# Schematic_Lithium-wemos-shield.net
KiCad netlist of a schematic drawn in EasyEDA
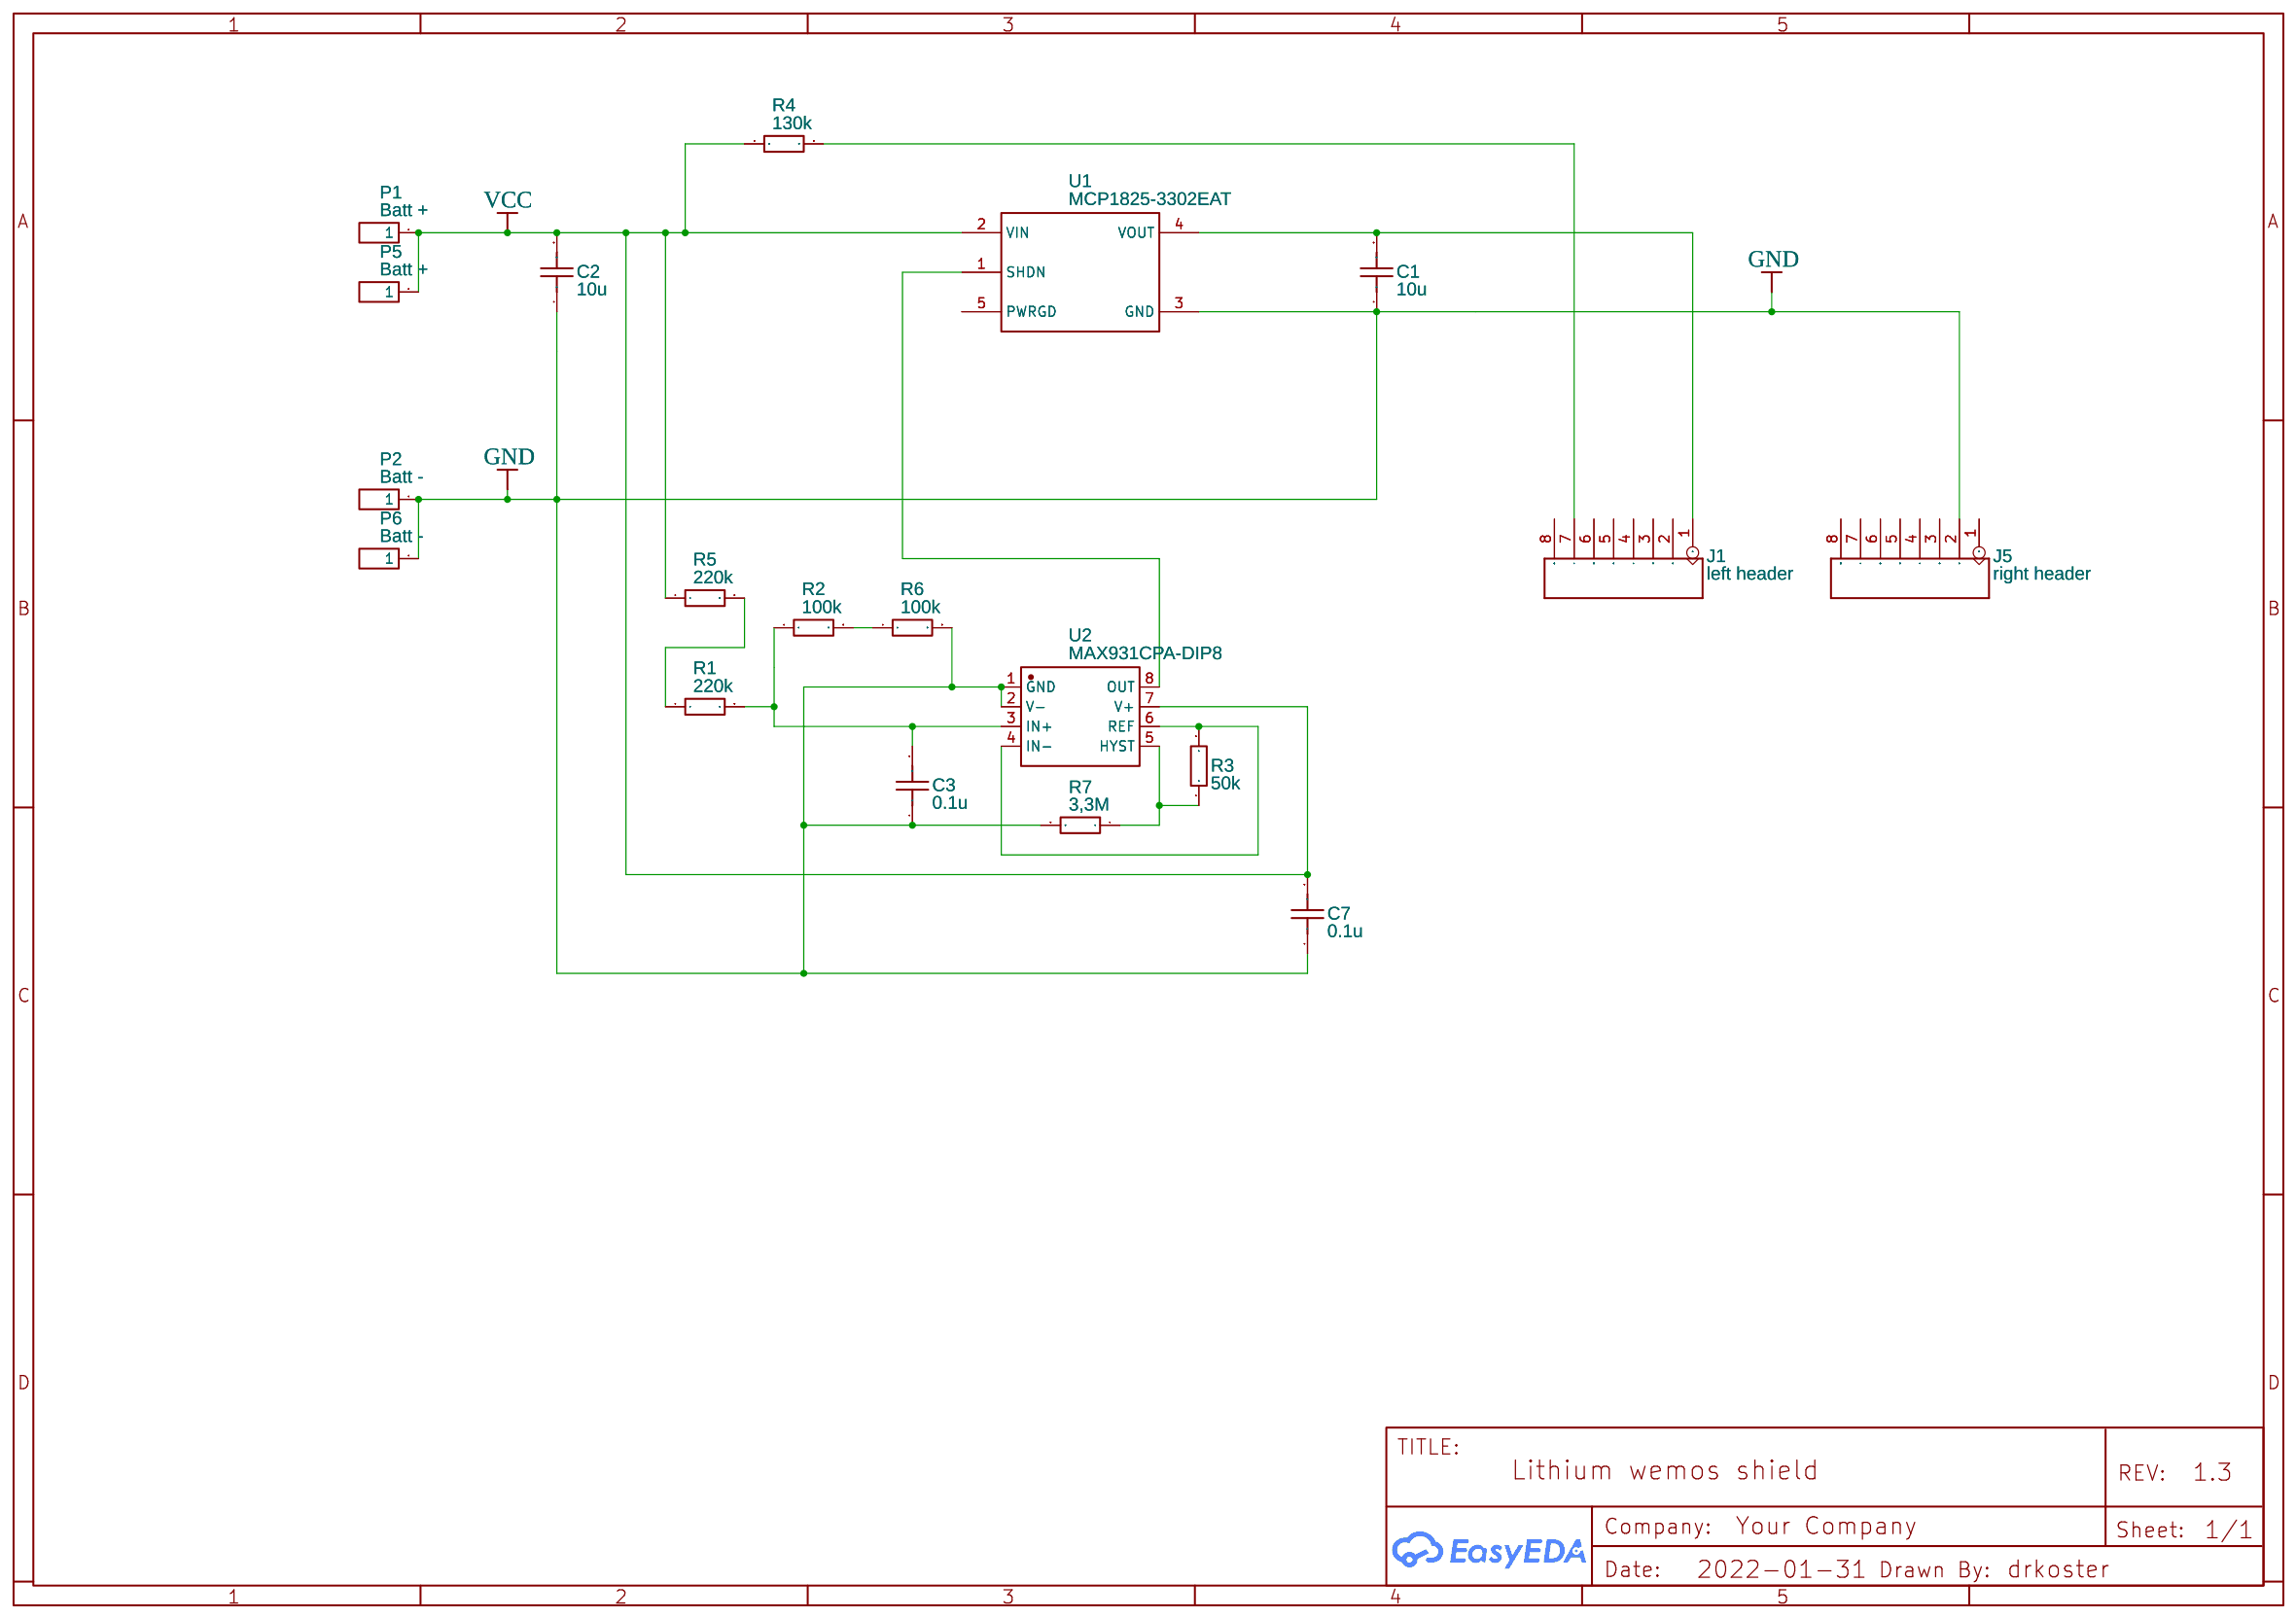
[diagram p0: schematic sheet]

(export (version "E")
  (design (tool "Eeschema 10.0.6"))
  (components
    (comp (ref "C1")
      (value "10u")
      (fields (field (name "BOM_Manufacturer Part") "?"))
      (libsource (lib "") (part "Cap_RAD-0.1_US"))
    )
    (comp (ref "C2")
      (value "10u")
      (fields (field (name "BOM_Manufacturer Part") "?"))
      (libsource (lib "") (part "Cap_RAD-0.1_US"))
    )
    (comp (ref "C3")
      (value "0.1u")
      (fields (field (name "BOM_Manufacturer Part") "?"))
      (libsource (lib "") (part "Cap_RAD-0.1_US"))
    )
    (comp (ref "C7")
      (value "0.1u")
      (fields (field (name "BOM_Manufacturer Part") "?"))
      (libsource (lib "") (part "Cap_RAD-0.1_US"))
    )
    (comp (ref "J1")
      (value "left header")
      (fields (field (name "BOM_Manufacturer Part") "F185-1108A0BSYA5"))
      (libsource (lib "") (part "Unknown_815_-530"))
    )
    (comp (ref "J5")
      (value "right header")
      (fields (field (name "BOM_Manufacturer Part") "F185-1108A0BSYA5"))
      (libsource (lib "") (part "Unknown_960_-530"))
    )
    (comp (ref "P1")
      (value "Batt +")
      (fields
        (field (name "BOM_Manufacturer Part") "Header-Male-2.54_1x1")
        (field (name "BOM_Supplier Part") "C81276")
      )
      (libsource (lib "") (part "Unknown_190_-695"))
    )
    (comp (ref "P2")
      (value "Batt -")
      (fields
        (field (name "BOM_Manufacturer Part") "Header-Male-2.54_1x1")
        (field (name "BOM_Supplier Part") "C81276")
      )
      (libsource (lib "") (part "Unknown_190_-560"))
    )
    (comp (ref "P5")
      (value "Batt +")
      (fields
        (field (name "BOM_Manufacturer Part") "Header-Male-2.54_1x1")
        (field (name "BOM_Supplier Part") "C81276")
      )
      (libsource (lib "") (part "Unknown_190_-665"))
    )
    (comp (ref "P6")
      (value "Batt -")
      (fields
        (field (name "BOM_Manufacturer Part") "Header-Male-2.54_1x1")
        (field (name "BOM_Supplier Part") "C81276")
      )
      (libsource (lib "") (part "Unknown_190_-530"))
    )
    (comp (ref "R1")
      (value "220k")
      (fields
        (field (name "BOM_Manufacturer Part") "MF1W-5.1Ω±1%")
        (field (name "BOM_Supplier Part") "C127239")
      )
      (libsource (lib "") (part "MF1W-5.1Ω±1%"))
    )
    (comp (ref "R2")
      (value "100k")
      (fields
        (field (name "BOM_Manufacturer Part") "MF1W-5.1Ω±1%")
        (field (name "BOM_Supplier Part") "C127239")
      )
      (libsource (lib "") (part "MF1W-5.1Ω±1%"))
    )
    (comp (ref "R3")
      (value "50k")
      (fields
        (field (name "BOM_Manufacturer Part") "MF1W-5.1Ω±1%")
        (field (name "BOM_Supplier Part") "C127239")
      )
      (libsource (lib "") (part "MF1W-5.1Ω±1%_2"))
    )
    (comp (ref "R4")
      (value "130k")
      (fields
        (field (name "BOM_Manufacturer Part") "MF1W-5.1Ω±1%")
        (field (name "BOM_Supplier Part") "C127239")
      )
      (libsource (lib "") (part "MF1W-5.1Ω±1%"))
    )
    (comp (ref "R5")
      (value "220k")
      (fields
        (field (name "BOM_Manufacturer Part") "MF1W-5.1Ω±1%")
        (field (name "BOM_Supplier Part") "C127239")
      )
      (libsource (lib "") (part "MF1W-5.1Ω±1%"))
    )
    (comp (ref "R6")
      (value "100k")
      (fields
        (field (name "BOM_Manufacturer Part") "MF1W-5.1Ω±1%")
        (field (name "BOM_Supplier Part") "C127239")
      )
      (libsource (lib "") (part "MF1W-5.1Ω±1%"))
    )
    (comp (ref "R7")
      (value "3,3M")
      (fields
        (field (name "BOM_Manufacturer Part") "MF1W-5.1Ω±1%")
        (field (name "BOM_Supplier Part") "C127239")
      )
      (libsource (lib "") (part "MF1W-5.1Ω±1%_1"))
    )
    (comp (ref "U1") (value "MCP1825-3302EAT") (libsource (lib "") (part "MCP1825-3302EAT")))
    (comp (ref "U2")
      (value "MAX931CPA-DIP8")
      (fields
        (field (name "BOM_Manufacturer Part") "MAX931CPA")
        (field (name "BOM_Supplier Part") "700-MAX931CPA")
      )
      (libsource (lib "") (part "MAX931CPA-DIP8"))
    )
  )
  (nets
    (net (code "1") (name "GND") (class "Default")
      (node (ref "C1") (pin "1") (pinfunction "1_1") (pintype "unspecified"))
      (node (ref "C2") (pin "1") (pinfunction "1_1") (pintype "unspecified"))
      (node (ref "C3") (pin "1") (pinfunction "1_1") (pintype "unspecified"))
      (node (ref "C7") (pin "1") (pinfunction "1_1") (pintype "unspecified"))
      (node (ref "J5") (pin "2") (pinfunction "2_2") (pintype "unspecified"))
      (node (ref "P2") (pin "1") (pinfunction "1_1") (pintype "input"))
      (node (ref "P6") (pin "1") (pinfunction "1_1") (pintype "input"))
      (node (ref "R6") (pin "2") (pinfunction "2_2") (pintype "input"))
      (node (ref "R7") (pin "2") (pinfunction "2_2") (pintype "input"))
      (node (ref "U1") (pin "3") (pinfunction "GND_3") (pintype "passive"))
      (node (ref "U2") (pin "1") (pinfunction "GND_1") (pintype "unspecified"))
      (node (ref "U2") (pin "2") (pinfunction "V-_2") (pintype "unspecified"))
    )
    (net (code "2") (name "Net-(J1-Pad7)") (class "Default")
      (node (ref "J1") (pin "7") (pinfunction "7_7") (pintype "unspecified"))
      (node (ref "R4") (pin "2") (pinfunction "2_2") (pintype "input"))
    )
    (net (code "3") (name "Net-(R1-Pad1)") (class "Default")
      (node (ref "R1") (pin "1") (pinfunction "1_1") (pintype "input"))
      (node (ref "R5") (pin "2") (pinfunction "2_2") (pintype "input"))
    )
    (net (code "4") (name "Net-(R2-Pad2)") (class "Default")
      (node (ref "R2") (pin "2") (pinfunction "2_2") (pintype "input"))
      (node (ref "R6") (pin "1") (pinfunction "1_1") (pintype "input"))
    )
    (net (code "5") (name "Net-(U1-SHDN)") (class "Default")
      (node (ref "U1") (pin "1") (pinfunction "SHDN_1") (pintype "unspecified"))
      (node (ref "U2") (pin "8") (pinfunction "OUT_8") (pintype "unspecified"))
    )
    (net (code "6") (name "Net-(U1-VOUT)") (class "Default")
      (node (ref "C1") (pin "2") (pinfunction "2_2") (pintype "unspecified"))
      (node (ref "J1") (pin "1") (pinfunction "1_1") (pintype "unspecified"))
      (node (ref "U1") (pin "4") (pinfunction "VOUT_4") (pintype "passive"))
    )
    (net (code "7") (name "Net-(U2-HYST)") (class "Default")
      (node (ref "R3") (pin "1") (pinfunction "1_1") (pintype "input"))
      (node (ref "R7") (pin "1") (pinfunction "1_1") (pintype "input"))
      (node (ref "U2") (pin "5") (pinfunction "HYST_5") (pintype "unspecified"))
    )
    (net (code "8") (name "Net-(U2-IN+)") (class "Default")
      (node (ref "C3") (pin "2") (pinfunction "2_2") (pintype "unspecified"))
      (node (ref "R1") (pin "2") (pinfunction "2_2") (pintype "input"))
      (node (ref "R2") (pin "1") (pinfunction "1_1") (pintype "input"))
      (node (ref "U2") (pin "3") (pinfunction "IN+_3") (pintype "unspecified"))
    )
    (net (code "9") (name "Net-(U2-IN-)") (class "Default")
      (node (ref "R3") (pin "2") (pinfunction "2_2") (pintype "input"))
      (node (ref "U2") (pin "4") (pinfunction "IN-_4") (pintype "unspecified"))
      (node (ref "U2") (pin "6") (pinfunction "REF_6") (pintype "unspecified"))
    )
    (net (code "10") (name "VCC") (class "Default")
      (node (ref "C2") (pin "2") (pinfunction "2_2") (pintype "unspecified"))
      (node (ref "C7") (pin "2") (pinfunction "2_2") (pintype "unspecified"))
      (node (ref "P1") (pin "1") (pinfunction "1_1") (pintype "input"))
      (node (ref "P5") (pin "1") (pinfunction "1_1") (pintype "input"))
      (node (ref "R4") (pin "1") (pinfunction "1_1") (pintype "input"))
      (node (ref "R5") (pin "1") (pinfunction "1_1") (pintype "input"))
      (node (ref "U1") (pin "2") (pinfunction "VIN_2") (pintype "passive"))
      (node (ref "U2") (pin "7") (pinfunction "V+_7") (pintype "unspecified"))
    )
    (net (code "11") (name "unconnected-(J1-Pad2)") (class "Default")
      (node (ref "J1") (pin "2") (pinfunction "2_2") (pintype "unspecified"))
    )
    (net (code "12") (name "unconnected-(J1-Pad3)") (class "Default")
      (node (ref "J1") (pin "3") (pinfunction "3_3") (pintype "unspecified"))
    )
    (net (code "13") (name "unconnected-(J1-Pad4)") (class "Default")
      (node (ref "J1") (pin "4") (pinfunction "4_4") (pintype "unspecified"))
    )
    (net (code "14") (name "unconnected-(J1-Pad5)") (class "Default")
      (node (ref "J1") (pin "5") (pinfunction "5_5") (pintype "unspecified"))
    )
    (net (code "15") (name "unconnected-(J1-Pad6)") (class "Default")
      (node (ref "J1") (pin "6") (pinfunction "6_6") (pintype "unspecified"))
    )
    (net (code "16") (name "unconnected-(J1-Pad8)") (class "Default")
      (node (ref "J1") (pin "8") (pinfunction "8_8") (pintype "unspecified"))
    )
    (net (code "17") (name "unconnected-(J5-Pad1)") (class "Default")
      (node (ref "J5") (pin "1") (pinfunction "1_1") (pintype "unspecified"))
    )
    (net (code "18") (name "unconnected-(J5-Pad3)") (class "Default")
      (node (ref "J5") (pin "3") (pinfunction "3_3") (pintype "unspecified"))
    )
    (net (code "19") (name "unconnected-(J5-Pad4)") (class "Default")
      (node (ref "J5") (pin "4") (pinfunction "4_4") (pintype "unspecified"))
    )
    (net (code "20") (name "unconnected-(J5-Pad5)") (class "Default")
      (node (ref "J5") (pin "5") (pinfunction "5_5") (pintype "unspecified"))
    )
    (net (code "21") (name "unconnected-(J5-Pad6)") (class "Default")
      (node (ref "J5") (pin "6") (pinfunction "6_6") (pintype "unspecified"))
    )
    (net (code "22") (name "unconnected-(J5-Pad7)") (class "Default")
      (node (ref "J5") (pin "7") (pinfunction "7_7") (pintype "unspecified"))
    )
    (net (code "23") (name "unconnected-(J5-Pad8)") (class "Default")
      (node (ref "J5") (pin "8") (pinfunction "8_8") (pintype "unspecified"))
    )
    (net (code "24") (name "unconnected-(U1-PWRGD-Pad5)") (class "Default")
      (node (ref "U1") (pin "5") (pinfunction "PWRGD_5") (pintype "passive"))
    )
  )
)
